# Connectors.net
KiCad netlist of a schematic drawn in Altium Designer
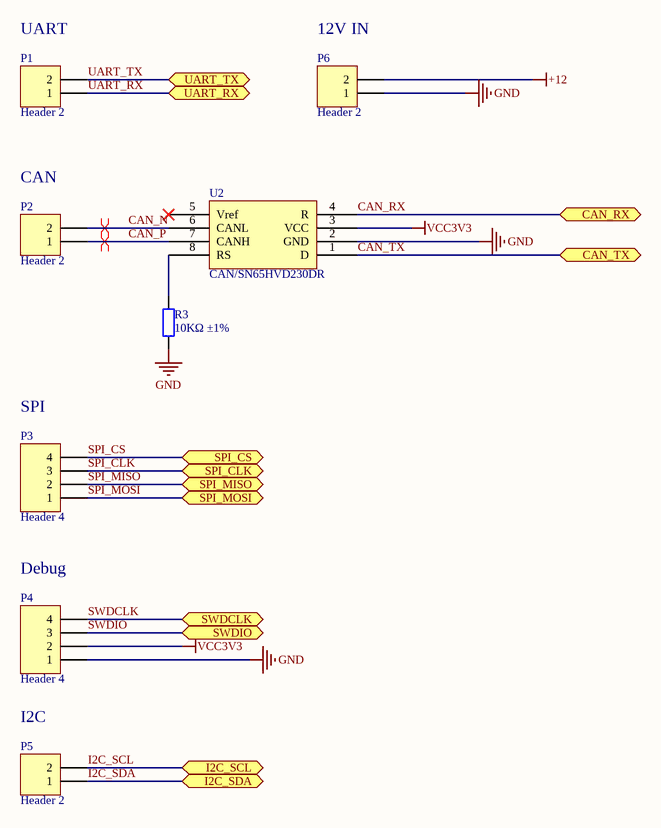
[diagram p0: Connectors.SchDoc]

(export (version "E")
  (design (tool "Eeschema 10.0.6"))
  (components
    (comp (ref "P1")
      (value "Header 2")
      (footprint "HDR1X2")
      (description "Header, 2-Pin")
      (fields (field (name "PUBLISHER") "Altium Limited"))
      (libsource (lib "Miscellaneous Connectors") (part "Header 2"))
    )
    (comp (ref "P2")
      (value "Header 2")
      (footprint "HDR1X2")
      (description "Header, 2-Pin")
      (fields (field (name "PUBLISHER") "Altium Limited"))
      (libsource (lib "Miscellaneous Connectors") (part "Header 2"))
    )
    (comp (ref "P3")
      (value "Header 4")
      (footprint "HDR1X4")
      (description "Header, 4-Pin")
      (fields (field (name "PUBLISHER") "Altium Limited"))
      (libsource (lib "Miscellaneous Connectors") (part "Header 4"))
    )
    (comp (ref "P4")
      (value "Header 4")
      (footprint "HDR1X4")
      (description "Header, 4-Pin")
      (fields (field (name "PUBLISHER") "Altium Limited"))
      (libsource (lib "Miscellaneous Connectors") (part "Header 4"))
    )
    (comp (ref "P5")
      (value "Header 2")
      (footprint "HDR1X2")
      (description "Header, 2-Pin")
      (fields (field (name "PUBLISHER") "Altium Limited"))
      (libsource (lib "Miscellaneous Connectors") (part "Header 2"))
    )
    (comp (ref "P6")
      (value "Header 2")
      (footprint "HDR1X2")
      (description "Header, 2-Pin")
      (fields (field (name "PUBLISHER") "Altium Limited"))
      (libsource (lib "Miscellaneous Connectors") (part "Header 2"))
    )
    (comp (ref "R3")
      (value "10KΩ ±1%")
      (footprint "0402_R")
      (description "Chip resistor")
      (fields (field (name "MANUFACTURER") "Uniroyal Elec") (field (name "PARTNUMBER") "0402WGF1002TCE"))
      (libsource (lib "Miscellaneous Devices LC") (part "0402 10K (1002) 1%"))
    )
    (comp (ref "U2")
      (value "CAN/SN65HVD230DR")
      (footprint "SOIC-8_150mil")
      (description "CAN")
      (libsource (lib "Miscellaneous Devices LC") (part "CAN/SN65HVD230DR_[C12084]"))
    )
  )
  (nets
    (net (code "1") (name "+12") (class "Default")
      (node (ref "P6") (pin "2") (pinfunction "2_2") (pintype "passive"))
    )
    (net (code "2") (name "/CAN_N") (class "Default")
      (node (ref "P2") (pin "2") (pinfunction "2_2") (pintype "passive"))
      (node (ref "U2") (pin "6") (pinfunction "CANL_6") (pintype "passive"))
    )
    (net (code "3") (name "/CAN_P") (class "Default")
      (node (ref "P2") (pin "1") (pinfunction "1_1") (pintype "passive"))
      (node (ref "U2") (pin "7") (pinfunction "CANH_7") (pintype "passive"))
    )
    (net (code "4") (name "/CAN_RX") (class "Default")
      (node (ref "U2") (pin "4") (pinfunction "R_4") (pintype "passive"))
    )
    (net (code "5") (name "/CAN_TX") (class "Default")
      (node (ref "U2") (pin "1") (pinfunction "D_1") (pintype "passive"))
    )
    (net (code "6") (name "/I2C_SCL") (class "Default")
      (node (ref "P5") (pin "2") (pinfunction "2_2") (pintype "passive"))
    )
    (net (code "7") (name "/I2C_SDA") (class "Default")
      (node (ref "P5") (pin "1") (pinfunction "1_1") (pintype "passive"))
    )
    (net (code "8") (name "/SPI_CLK") (class "Default")
      (node (ref "P3") (pin "3") (pinfunction "3_3") (pintype "passive"))
    )
    (net (code "9") (name "/SPI_CS") (class "Default")
      (node (ref "P3") (pin "4") (pinfunction "4_4") (pintype "passive"))
    )
    (net (code "10") (name "/SPI_MISO") (class "Default")
      (node (ref "P3") (pin "2") (pinfunction "2_2") (pintype "passive"))
    )
    (net (code "11") (name "/SPI_MOSI") (class "Default")
      (node (ref "P3") (pin "1") (pinfunction "1_1") (pintype "passive"))
    )
    (net (code "12") (name "/SWDCLK") (class "Default")
      (node (ref "P4") (pin "4") (pinfunction "4_4") (pintype "passive"))
    )
    (net (code "13") (name "/SWDIO") (class "Default")
      (node (ref "P4") (pin "3") (pinfunction "3_3") (pintype "passive"))
    )
    (net (code "14") (name "/UART_RX") (class "Default")
      (node (ref "P1") (pin "1") (pinfunction "1_1") (pintype "passive"))
    )
    (net (code "15") (name "/UART_TX") (class "Default")
      (node (ref "P1") (pin "2") (pinfunction "2_2") (pintype "passive"))
    )
    (net (code "16") (name "GND") (class "Default")
      (node (ref "P4") (pin "1") (pinfunction "1_1") (pintype "passive"))
      (node (ref "P6") (pin "1") (pinfunction "1_1") (pintype "passive"))
      (node (ref "R3") (pin "1") (pinfunction "1_1") (pintype "passive"))
      (node (ref "U2") (pin "2") (pinfunction "GND_2") (pintype "passive"))
    )
    (net (code "17") (name "Net-(U2-RS)") (class "Default")
      (node (ref "R3") (pin "2") (pinfunction "2_2") (pintype "passive"))
      (node (ref "U2") (pin "8") (pinfunction "RS_8") (pintype "passive"))
    )
    (net (code "18") (name "VCC3V3") (class "Default")
      (node (ref "P4") (pin "2") (pinfunction "2_2") (pintype "passive"))
      (node (ref "U2") (pin "3") (pinfunction "VCC_3") (pintype "passive"))
    )
    (net (code "19") (name "unconnected-(U2-Vref-Pad5)") (class "Default")
      (node (ref "U2") (pin "5") (pinfunction "Vref_5") (pintype "passive+no_connect"))
    )
  )
)
